# design.net
KiCad netlist of a schematic drawn in Altium Designer
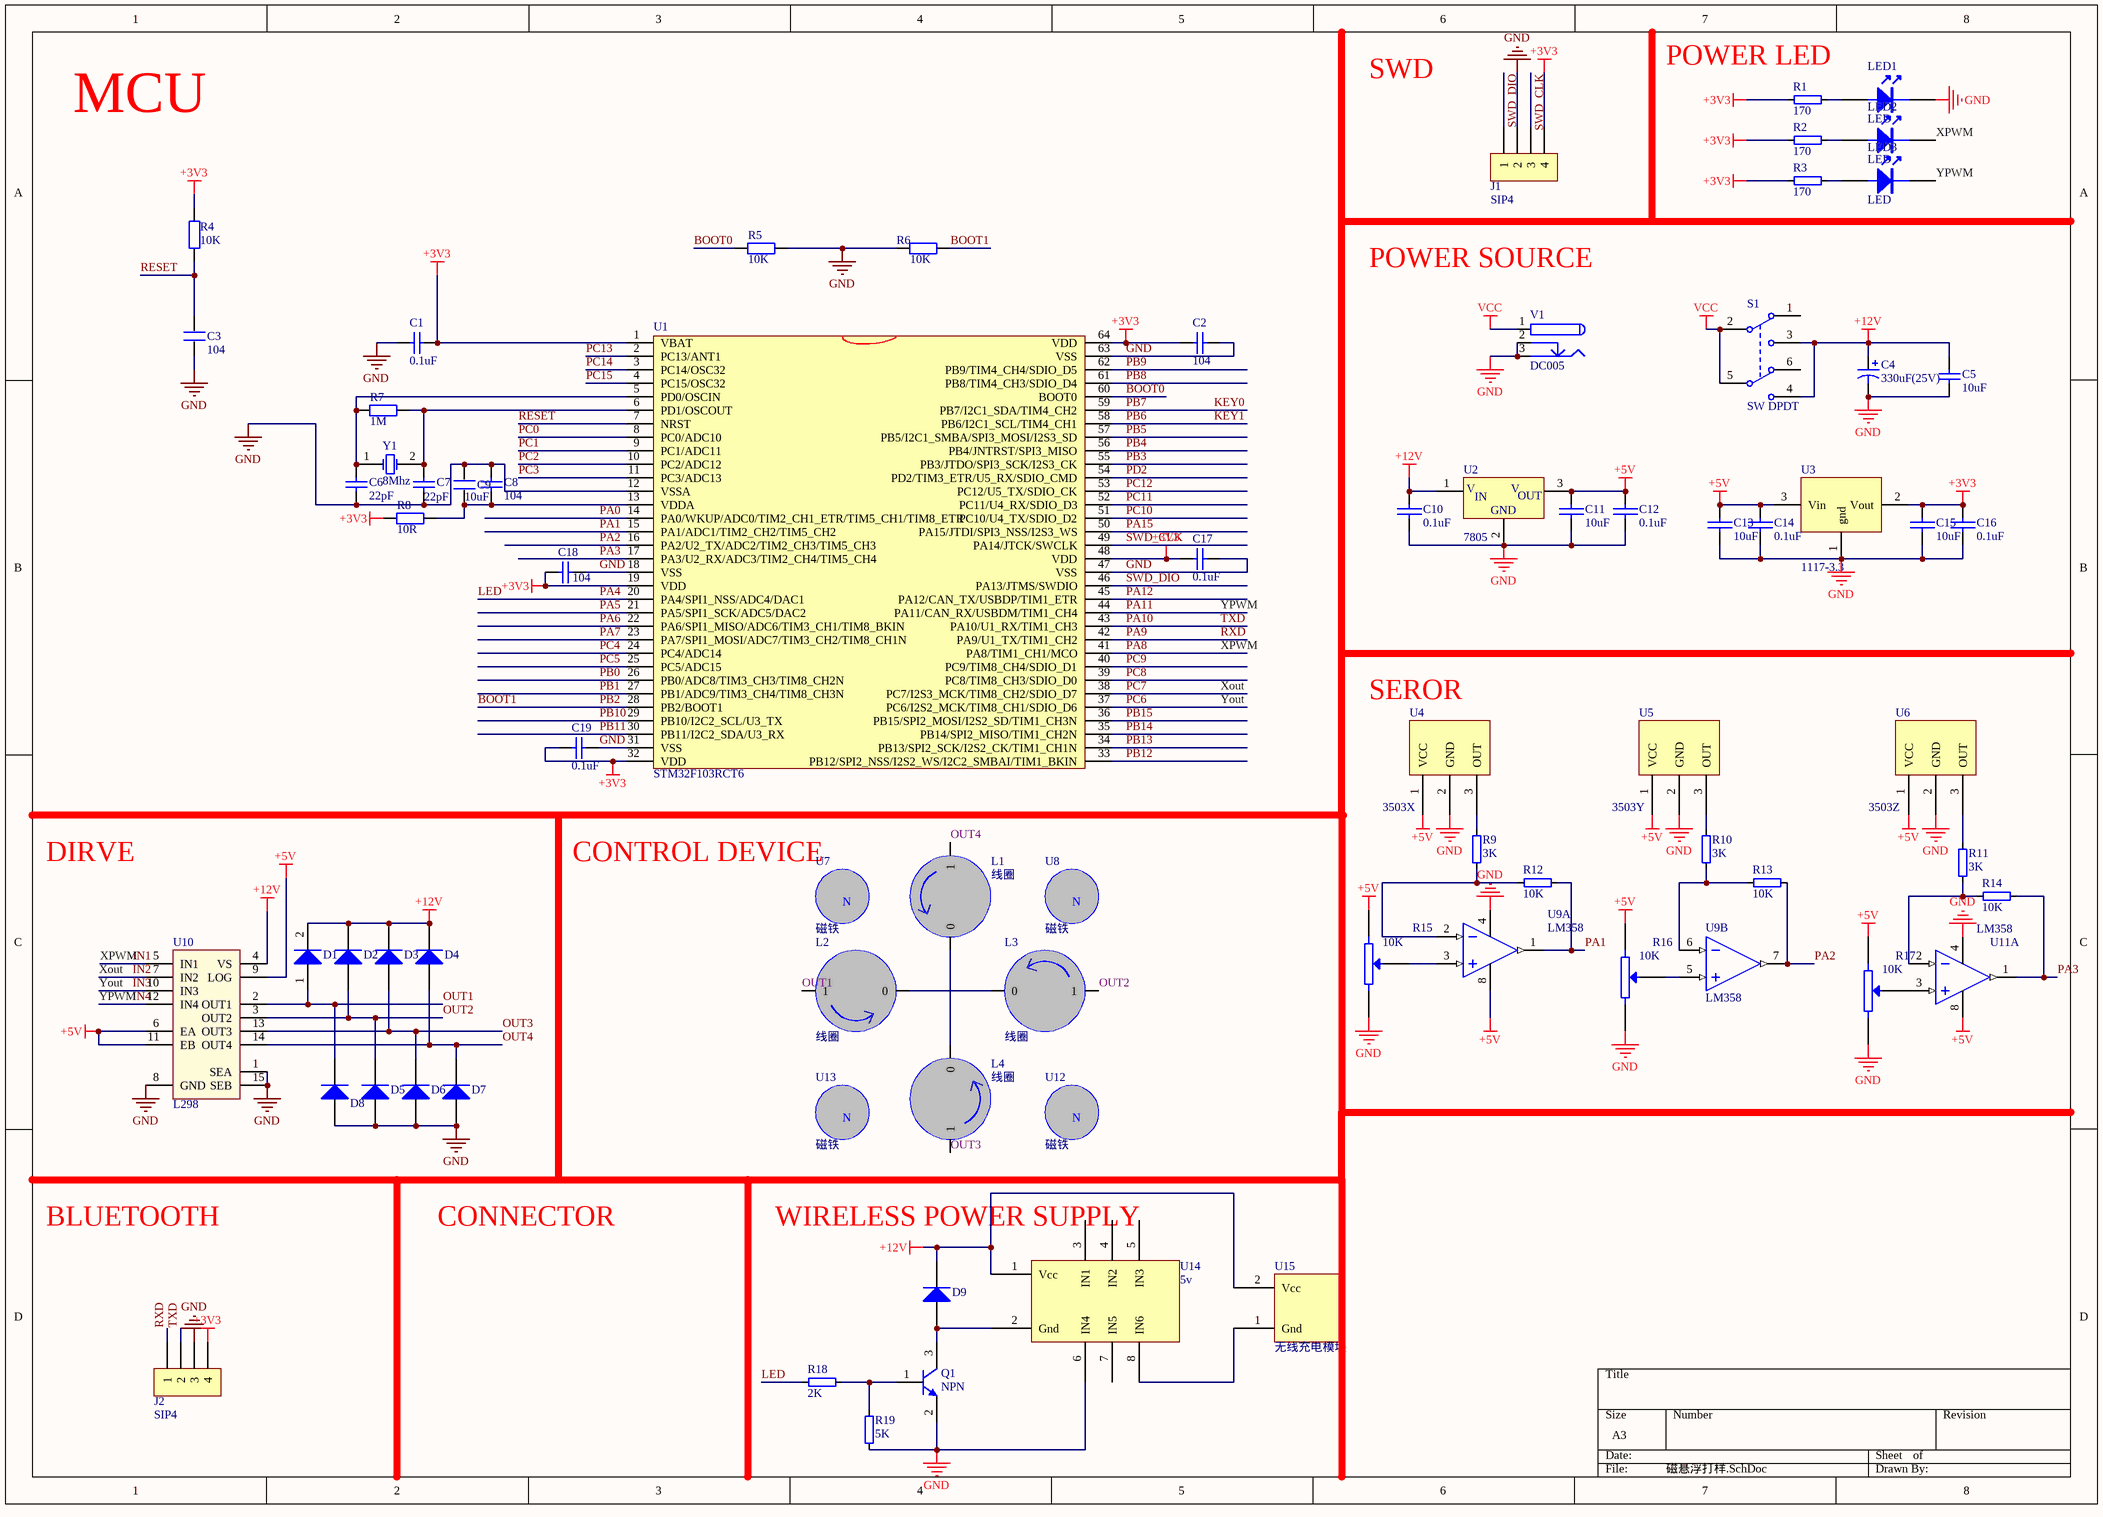
[diagram p0: 磁悬浮打样.SchDoc]

(export (version "E")
  (design (tool "Eeschema 10.0.6"))
  (components
    (comp (ref "C1")
      (value "0.1uF")
      (footprint "CAP_0805")
      (description "Capacitor")
      (fields (field (name "Comment") "Cap") (field (name "PUBLISHER") "Altium Limited"))
      (libsource (lib "FLY") (part "Cap"))
    )
    (comp (ref "C2")
      (value "104")
      (footprint "CAP_0805")
      (description "Capacitor")
      (fields (field (name "Comment") "Cap") (field (name "PUBLISHER") "Altium Limited"))
      (libsource (lib "FLY") (part "Cap_1"))
    )
    (comp (ref "C3") (value "104") (footprint "CAP_0805") (libsource (lib "液晶模块封装库") (part "C")))
    (comp (ref "C4")
      (value "330uF(25V)")
      (footprint "CAP_ELEC_AL_6.3x4.2")
      (description "Polarized Capacitor (Radial)")
      (fields (field (name "Comment") "Cap Pol1") (field (name "PUBLISHER") "Altium Limited"))
      (libsource (lib "FLY") (part "Cap Pol1_1"))
    )
    (comp (ref "C5")
      (value "10uF")
      (footprint "CAP_0805")
      (description "Capacitor")
      (fields (field (name "Comment") "Cap") (field (name "PUBLISHER") "Altium Limited"))
      (libsource (lib "FLY") (part "Cap_2"))
    )
    (comp (ref "C6")
      (value "22pF")
      (footprint "CAP_0805")
      (description "Capacitor")
      (fields (field (name "Comment") "Cap") (field (name "PUBLISHER") "Altium Limited"))
      (libsource (lib "FLY") (part "Cap_3"))
    )
    (comp (ref "C7")
      (value "22pF")
      (footprint "CAP_0805")
      (description "Capacitor")
      (fields (field (name "Comment") "Cap") (field (name "PUBLISHER") "Altium Limited"))
      (libsource (lib "FLY") (part "Cap_3"))
    )
    (comp (ref "C8")
      (value "104")
      (footprint "CAP_0805")
      (description "Capacitor")
      (fields (field (name "Comment") "Cap") (field (name "PUBLISHER") "Altium Limited"))
      (libsource (lib "FLY") (part "Cap_3"))
    )
    (comp (ref "C9") (value "10uF") (footprint "CAP_0805") (libsource (lib "ENC28J60网络模块封装库") (part "C")))
    (comp (ref "C10")
      (value "0.1uF")
      (footprint "CAP_0805")
      (libsource (lib "altium-import") (part "root_0_CAP_"))
    )
    (comp (ref "C11") (value "10uF") (footprint "CAP_0805") (libsource (lib "*") (part "CAP")))
    (comp (ref "C12") (value "0.1uF") (footprint "CAP_0805") (libsource (lib "*") (part "CAP")))
    (comp (ref "C13") (value "10uF") (footprint "CAP_0805") (libsource (lib "*") (part "CAP")))
    (comp (ref "C14") (value "0.1uF") (footprint "CAP_0805") (libsource (lib "*") (part "CAP")))
    (comp (ref "C15") (value "10uF") (footprint "CAP_0805") (libsource (lib "*") (part "CAP")))
    (comp (ref "C16") (value "0.1uF") (footprint "CAP_0805") (libsource (lib "*") (part "CAP")))
    (comp (ref "C17")
      (value "0.1uF")
      (footprint "CAP_0805")
      (description "Capacitor")
      (fields (field (name "Comment") "Cap") (field (name "PUBLISHER") "Altium Limited"))
      (libsource (lib "FLY") (part "Cap_1"))
    )
    (comp (ref "C18")
      (value "104")
      (footprint "CAP_0805")
      (description "Capacitor")
      (fields (field (name "Comment") "Cap") (field (name "PUBLISHER") "Altium Limited"))
      (libsource (lib "FLY") (part "Cap_1"))
    )
    (comp (ref "C19")
      (value "0.1uF")
      (footprint "CAP_0805")
      (description "Capacitor")
      (fields (field (name "Comment") "Cap") (field (name "PUBLISHER") "Altium Limited"))
      (libsource (lib "FLY") (part "Cap_1"))
    )
    (comp (ref "D1")
      (value "Diode")
      (footprint "PCB11:1N5819")
      (description "Default Diode")
      (fields (field (name "PUBLISHER") "Altium Limited"))
      (libsource (lib "") (part "Diode_1"))
    )
    (comp (ref "D2")
      (value "Diode")
      (footprint "PCB11:1N5819")
      (description "Default Diode")
      (fields (field (name "PUBLISHER") "Altium Limited"))
      (libsource (lib "*") (part "Diode"))
    )
    (comp (ref "D3")
      (value "Diode")
      (footprint "PCB11:1N5819")
      (description "Default Diode")
      (fields (field (name "PUBLISHER") "Altium Limited"))
      (libsource (lib "*") (part "Diode"))
    )
    (comp (ref "D4")
      (value "Diode")
      (footprint "PCB11:1N5819")
      (description "Default Diode")
      (fields (field (name "PUBLISHER") "Altium Limited"))
      (libsource (lib "*") (part "Diode"))
    )
    (comp (ref "D5")
      (value "Diode")
      (footprint "PCB11:1N5819")
      (description "Default Diode")
      (fields (field (name "PUBLISHER") "Altium Limited"))
      (libsource (lib "*") (part "Diode"))
    )
    (comp (ref "D6")
      (value "Diode")
      (footprint "PCB11:1N5819")
      (description "Default Diode")
      (fields (field (name "PUBLISHER") "Altium Limited"))
      (libsource (lib "*") (part "Diode"))
    )
    (comp (ref "D7")
      (value "Diode")
      (footprint "PCB11:1N5819")
      (description "Default Diode")
      (fields (field (name "PUBLISHER") "Altium Limited"))
      (libsource (lib "*") (part "Diode"))
    )
    (comp (ref "D8")
      (value "Diode")
      (footprint "PCB11:1N5819")
      (description "Default Diode")
      (fields (field (name "PUBLISHER") "Altium Limited"))
      (libsource (lib "*") (part "Diode"))
    )
    (comp (ref "D9")
      (value "Diode")
      (footprint "PCB11:1N5819")
      (description "Default Diode")
      (fields (field (name "PUBLISHER") "Altium Limited"))
      (libsource (lib "*") (part "Diode"))
    )
    (comp (ref "J1")
      (value "SIP4")
      (footprint "HDR1X4_180_2.54")
      (description "jointbar")
      (libsource (lib "接口") (part "SIP4"))
    )
    (comp (ref "J2")
      (value "SIP4")
      (footprint "298N:SIP4 H")
      (description "jointbar")
      (libsource (lib "接口") (part "SIP4"))
    )
    (comp (ref "L1") (value "线圈") (footprint "线圈") (libsource (lib "红外报警") (part "线圈")))
    (comp (ref "L2") (value "线圈") (footprint "线圈") (libsource (lib "红外报警") (part "线圈")))
    (comp (ref "L3") (value "线圈") (footprint "线圈") (libsource (lib "红外报警") (part "线圈")))
    (comp (ref "L4") (value "线圈") (footprint "线圈") (libsource (lib "红外报警") (part "线圈")))
    (comp (ref "LED1")
      (value "LED")
      (footprint "LED0805蓝")
      (libsource (lib "阻容LED（集成）_Library") (part "LED"))
    )
    (comp (ref "LED2")
      (value "LED")
      (footprint "LED0805蓝")
      (libsource (lib "阻容LED（集成）_Library") (part "LED"))
    )
    (comp (ref "LED3")
      (value "LED")
      (footprint "LED0805蓝")
      (libsource (lib "阻容LED（集成）_Library") (part "LED"))
    )
    (comp (ref "Q1")
      (value "NPN")
      (footprint "SOT23-3")
      (description "贴片三极管")
      (fields (field (name "PUBLISHER") "Altium Limited"))
      (libsource (lib "主库（集成）_Library") (part "NPN1"))
    )
    (comp (ref "R1") (value "170") (footprint "PCB_Passive:RES_0805") (libsource (lib "*") (part "RESistor")))
    (comp (ref "R2") (value "170") (footprint "PCB_Passive:RES_0805") (libsource (lib "*") (part "RESistor")))
    (comp (ref "R3") (value "170") (footprint "PCB_Passive:RES_0805") (libsource (lib "*") (part "RESistor")))
    (comp (ref "R4")
      (value "10K")
      (footprint "RES_0805")
      (description "Resistor")
      (fields (field (name "Comment") "Res2") (field (name "PUBLISHER") "Altium Limited"))
      (libsource (lib "") (part "Res2_1_1"))
    )
    (comp (ref "R5")
      (value "10K")
      (footprint "RES_0805")
      (description "Resistor")
      (fields (field (name "Comment") "Res2") (field (name "PUBLISHER") "Altium Limited"))
      (libsource (lib "FLY") (part "Res2"))
    )
    (comp (ref "R6")
      (value "10K")
      (footprint "RES_0805")
      (description "Resistor")
      (fields (field (name "Comment") "Res2") (field (name "PUBLISHER") "Altium Limited"))
      (libsource (lib "FLY") (part "Res2"))
    )
    (comp (ref "R7")
      (value "1M")
      (footprint "RES_0805")
      (description "Resistor")
      (fields (field (name "Comment") "Res2") (field (name "PUBLISHER") "Altium Limited"))
      (libsource (lib "FLY") (part "Res2"))
    )
    (comp (ref "R8")
      (value "10R")
      (footprint "RES_0805")
      (description "Resistor")
      (fields (field (name "Comment") "Res2") (field (name "PUBLISHER") "Altium Limited"))
      (libsource (lib "FLY") (part "Res2_1"))
    )
    (comp (ref "R9") (value "3K") (footprint "PCB_Passive:RES_0805") (libsource (lib "*") (part "RESistor")))
    (comp (ref "R10") (value "3K") (footprint "PCB_Passive:RES_0805") (libsource (lib "*") (part "RESistor")))
    (comp (ref "R11") (value "3K") (footprint "PCB_Passive:RES_0805") (libsource (lib "*") (part "RESistor")))
    (comp (ref "R12")
      (value "10K")
      (footprint "PCB_Passive:RES_0805")
      (libsource (lib "*") (part "RESistor"))
    )
    (comp (ref "R13")
      (value "10K")
      (footprint "PCB_Passive:RES_0805")
      (libsource (lib "*") (part "RESistor"))
    )
    (comp (ref "R14")
      (value "10K")
      (footprint "PCB_Passive:RES_0805")
      (libsource (lib "*") (part "RESistor"))
    )
    (comp (ref "R15")
      (value "10K")
      (footprint "VR")
      (description "Potentiometer")
      (libsource (lib "原理图") (part "RESVR"))
    )
    (comp (ref "R16")
      (value "10K")
      (footprint "VR")
      (description "Potentiometer")
      (libsource (lib "原理图") (part "RESVR"))
    )
    (comp (ref "R17")
      (value "10K")
      (footprint "VR")
      (description "Potentiometer")
      (libsource (lib "原理图") (part "RESVR"))
    )
    (comp (ref "R18") (value "2K") (footprint "PCB_Passive:RES_0805") (libsource (lib "*") (part "RESistor")))
    (comp (ref "R19") (value "5K") (footprint "PCB_Passive:RES_0805") (libsource (lib "*") (part "RESistor")))
    (comp (ref "S1")
      (value "SW DPDT")
      (footprint "SW6")
      (description "Switch")
      (fields (field (name "PUBLISHER") "Altium Limited"))
      (libsource (lib "原理图") (part "SW DPDT"))
    )
    (comp (ref "U1")
      (value "STM32F103RCT6")
      (footprint "LQFP64_L")
      (libsource (lib "MiniSTM32 V3.0封装库") (part "STM32F103RDT6"))
    )
    (comp (ref "U2") (value "7805") (footprint "TO-220") (libsource (lib "ADDA库") (part "7812")))
    (comp (ref "U3") (value "1117-3.3") (footprint "SOT223") (libsource (lib "298N") (part "1117")))
    (comp (ref "U4") (value "3503X") (footprint "TO-92UA") (libsource (lib "298N") (part "3503")))
    (comp (ref "U5") (value "3503Y") (footprint "TO-92UA") (libsource (lib "298N") (part "3503")))
    (comp (ref "U6") (value "3503Z") (footprint "TO-92UA") (libsource (lib "298N") (part "3503")))
    (comp (ref "U7") (value "磁铁") (footprint "磁铁") (libsource (lib "298N") (part "磁铁")))
    (comp (ref "U8") (value "磁铁") (footprint "磁铁") (libsource (lib "298N") (part "磁铁")))
    (comp (ref "U9")
      (value "LM358")
      (footprint "SOIC-8")
      (description "双运放")
      (libsource (lib "主库（集成）_Library") (part "LM358"))
    )
    (comp (ref "U10") (value "L298") (footprint "L298N") (libsource (lib "leelib") (part "L298")))
    (comp (ref "U11")
      (value "LM358")
      (footprint "SOIC-8")
      (description "双运放")
      (libsource (lib "主库（集成）_Library") (part "LM358"))
    )
    (comp (ref "U12") (value "磁铁") (footprint "磁铁") (libsource (lib "298N") (part "磁铁")))
    (comp (ref "U13") (value "磁铁") (footprint "磁铁") (libsource (lib "298N") (part "磁铁")))
    (comp (ref "U14") (value "5v") (footprint "relay-5v") (libsource (lib "298N") (part "relay-5V")))
    (comp (ref "U15") (value "无线充电模块") (footprint "无线充电模块") (libsource (lib "298N") (part "无线充电")))
    (comp (ref "V1") (value "DC005") (footprint "DC-005") (libsource (lib "原理图") (part "DC005")))
    (comp (ref "Y1")
      (value "8Mhz")
      (footprint "crystal")
      (description "Crystal Oscillator")
      (fields (field (name "PUBLISHER") "Altium Limited"))
      (libsource (lib "*") (part "XTAL"))
    )
  )
  (nets
    (net (code "1") (name "+3V3") (class "Default")
      (node (ref "C1") (pin "2") (pinfunction "2_2") (pintype "passive"))
      (node (ref "C15") (pin "1") (pinfunction "1_1") (pintype "passive"))
      (node (ref "C16") (pin "1") (pinfunction "1_1") (pintype "passive"))
      (node (ref "C17") (pin "1") (pinfunction "1_1") (pintype "passive"))
      (node (ref "C18") (pin "1") (pinfunction "1_1") (pintype "passive"))
      (node (ref "C19") (pin "1") (pinfunction "1_1") (pintype "passive"))
      (node (ref "C2") (pin "1") (pinfunction "1_1") (pintype "passive"))
      (node (ref "J1") (pin "4") (pinfunction "4_4") (pintype "passive"))
      (node (ref "J2") (pin "4") (pinfunction "4_4") (pintype "passive"))
      (node (ref "R1") (pin "1") (pinfunction "1_1") (pintype "passive"))
      (node (ref "R2") (pin "1") (pinfunction "1_1") (pintype "passive"))
      (node (ref "R3") (pin "1") (pinfunction "1_1") (pintype "passive"))
      (node (ref "R4") (pin "2") (pinfunction "2_2") (pintype "passive"))
      (node (ref "R8") (pin "1") (pinfunction "1_1") (pintype "passive"))
      (node (ref "U1") (pin "1") (pinfunction "VBAT_1") (pintype "passive"))
      (node (ref "U1") (pin "19") (pinfunction "VDD_19") (pintype "passive"))
      (node (ref "U1") (pin "32") (pinfunction "VDD_32") (pintype "passive"))
      (node (ref "U1") (pin "48") (pinfunction "VDD_48") (pintype "passive"))
      (node (ref "U1") (pin "64") (pinfunction "VDD_64") (pintype "passive"))
      (node (ref "U3") (pin "2") (pinfunction "Vout_2") (pintype "passive"))
    )
    (net (code "2") (name "+5V") (class "Default")
      (node (ref "C11") (pin "1") (pinfunction "1_1") (pintype "passive"))
      (node (ref "C12") (pin "1") (pinfunction "1_1") (pintype "passive"))
      (node (ref "C13") (pin "1") (pinfunction "1_1") (pintype "passive"))
      (node (ref "C14") (pin "1") (pinfunction "1_1") (pintype "passive"))
      (node (ref "R15") (pin "1") (pinfunction "1_1") (pintype "passive"))
      (node (ref "R16") (pin "1") (pinfunction "1_1") (pintype "passive"))
      (node (ref "R17") (pin "1") (pinfunction "1_1") (pintype "passive"))
      (node (ref "U10") (pin "11") (pinfunction "EB_11") (pintype "passive"))
      (node (ref "U10") (pin "6") (pinfunction "EA_6") (pintype "passive"))
      (node (ref "U10") (pin "9") (pinfunction "LOG_9") (pintype "passive"))
      (node (ref "U11") (pin "8") (pinfunction "V+_8") (pintype "passive"))
      (node (ref "U2") (pin "3") (pinfunction "VOUT_3") (pintype "passive"))
      (node (ref "U3") (pin "3") (pinfunction "Vin_3") (pintype "passive"))
      (node (ref "U4") (pin "1") (pinfunction "VCC_1") (pintype "passive"))
      (node (ref "U5") (pin "1") (pinfunction "VCC_1") (pintype "passive"))
      (node (ref "U6") (pin "1") (pinfunction "VCC_1") (pintype "passive"))
      (node (ref "U9") (pin "8") (pinfunction "V+_8") (pintype "passive"))
    )
    (net (code "3") (name "+12V") (class "Default")
      (node (ref "C10") (pin "1") (pinfunction "1_1") (pintype "passive"))
      (node (ref "C4") (pin "1") (pinfunction "1_1") (pintype "passive"))
      (node (ref "C5") (pin "2") (pinfunction "2_2") (pintype "passive"))
      (node (ref "D1") (pin "2") (pinfunction "K_2") (pintype "passive"))
      (node (ref "D2") (pin "2") (pinfunction "K_2") (pintype "passive"))
      (node (ref "D3") (pin "2") (pinfunction "K_2") (pintype "passive"))
      (node (ref "D4") (pin "2") (pinfunction "K_2") (pintype "passive"))
      (node (ref "D9") (pin "2") (pinfunction "K_2") (pintype "passive"))
      (node (ref "S1") (pin "3") (pinfunction "NO1_3") (pintype "passive"))
      (node (ref "S1") (pin "4") (pinfunction "NO2_4") (pintype "passive"))
      (node (ref "U10") (pin "4") (pinfunction "VS_4") (pintype "passive"))
      (node (ref "U14") (pin "1") (pinfunction "Vcc_1") (pintype "passive"))
      (node (ref "U15") (pin "2") (pinfunction "Vcc_2") (pintype "passive"))
      (node (ref "U2") (pin "1") (pinfunction "VIN_1") (pintype "passive"))
    )
    (net (code "4") (name "/BOOT0") (class "Default")
      (node (ref "R5") (pin "1") (pinfunction "1_1") (pintype "passive"))
      (node (ref "U1") (pin "60") (pinfunction "BOOT0_60") (pintype "passive"))
    )
    (net (code "5") (name "/BOOT1") (class "Default")
      (node (ref "R6") (pin "2") (pinfunction "2_2") (pintype "passive"))
      (node (ref "U1") (pin "28") (pinfunction "PB2/BOOT1_28") (pintype "passive"))
    )
    (net (code "6") (name "/IN1") (class "Default")
      (node (ref "LED2") (pin "K") (pinfunction "2_K") (pintype "passive"))
      (node (ref "U1") (pin "41") (pinfunction "PA8/TIM1_CH1/MCO_41") (pintype "passive"))
      (node (ref "U10") (pin "5") (pinfunction "IN1_5") (pintype "passive"))
    )
    (net (code "7") (name "/IN2") (class "Default")
      (node (ref "U1") (pin "38") (pinfunction "PC7/I2S3_MCK/TIM8_CH2/SDIO_D7_38") (pintype "passive"))
      (node (ref "U10") (pin "7") (pinfunction "IN2_7") (pintype "passive"))
    )
    (net (code "8") (name "/IN3") (class "Default")
      (node (ref "U1") (pin "37") (pinfunction "PC6/I2S2_MCK/TIM8_CH1/SDIO_D6_37") (pintype "passive"))
      (node (ref "U10") (pin "10") (pinfunction "IN3_10") (pintype "passive"))
    )
    (net (code "9") (name "/IN4") (class "Default")
      (node (ref "LED3") (pin "K") (pinfunction "2_K") (pintype "passive"))
      (node (ref "U1") (pin "44") (pinfunction "PA11/CAN_RX/USBDM/TIM1_CH4_44") (pintype "passive"))
      (node (ref "U10") (pin "12") (pinfunction "IN4_12") (pintype "passive"))
    )
    (net (code "10") (name "/KEY0") (class "Default")
      (node (ref "U1") (pin "59") (pinfunction "PB7/I2C1_SDA/TIM4_CH2_59") (pintype "passive"))
    )
    (net (code "11") (name "/KEY1") (class "Default")
      (node (ref "U1") (pin "58") (pinfunction "PB6/I2C1_SCL/TIM4_CH1_58") (pintype "passive"))
    )
    (net (code "12") (name "/LED") (class "Default")
      (node (ref "R18") (pin "2") (pinfunction "2_2") (pintype "passive"))
      (node (ref "U1") (pin "20") (pinfunction "PA4/SPI1_NSS/ADC4/DAC1_20") (pintype "passive"))
    )
    (net (code "13") (name "/OUT1") (class "Default")
      (node (ref "D1") (pin "1") (pinfunction "A_1") (pintype "passive"))
      (node (ref "D8") (pin "2") (pinfunction "K_2") (pintype "passive"))
      (node (ref "L2") (pin "1") (pinfunction "1_1") (pintype "passive"))
      (node (ref "U10") (pin "2") (pinfunction "OUT1_2") (pintype "passive"))
    )
    (net (code "14") (name "/OUT2") (class "Default")
      (node (ref "D2") (pin "1") (pinfunction "A_1") (pintype "passive"))
      (node (ref "D5") (pin "2") (pinfunction "K_2") (pintype "passive"))
      (node (ref "L3") (pin "1") (pinfunction "1_1") (pintype "passive"))
      (node (ref "U10") (pin "3") (pinfunction "OUT2_3") (pintype "passive"))
    )
    (net (code "15") (name "/OUT3") (class "Default")
      (node (ref "D3") (pin "1") (pinfunction "A_1") (pintype "passive"))
      (node (ref "D6") (pin "2") (pinfunction "K_2") (pintype "passive"))
      (node (ref "L4") (pin "1") (pinfunction "1_1") (pintype "passive"))
      (node (ref "U10") (pin "13") (pinfunction "OUT3_13") (pintype "passive"))
    )
    (net (code "16") (name "/OUT4") (class "Default")
      (node (ref "D4") (pin "1") (pinfunction "A_1") (pintype "passive"))
      (node (ref "D7") (pin "2") (pinfunction "K_2") (pintype "passive"))
      (node (ref "L1") (pin "1") (pinfunction "1_1") (pintype "passive"))
      (node (ref "U10") (pin "14") (pinfunction "OUT4_14") (pintype "passive"))
    )
    (net (code "17") (name "/PA0") (class "Default")
      (node (ref "U1") (pin "14") (pinfunction "PA0/WKUP/ADC0/TIM2_CH1_ETR/TIM5_CH1/TIM8_ETR_14") (pintype "passive"))
    )
    (net (code "18") (name "/PA1") (class "Default")
      (node (ref "R12") (pin "1") (pinfunction "1_1") (pintype "passive"))
      (node (ref "U1") (pin "15") (pinfunction "PA1/ADC1/TIM2_CH2/TIM5_CH2_15") (pintype "passive"))
      (node (ref "U9") (pin "1") (pinfunction "OUT_1") (pintype "output"))
    )
    (net (code "19") (name "/PA2") (class "Default")
      (node (ref "R13") (pin "1") (pinfunction "1_1") (pintype "passive"))
      (node (ref "U1") (pin "16") (pinfunction "PA2/U2_TX/ADC2/TIM2_CH3/TIM5_CH3_16") (pintype "passive"))
      (node (ref "U9") (pin "7") (pinfunction "OUT_7") (pintype "output"))
    )
    (net (code "20") (name "/PA3") (class "Default")
      (node (ref "R14") (pin "1") (pinfunction "1_1") (pintype "passive"))
      (node (ref "U1") (pin "17") (pinfunction "PA3/U2_RX/ADC3/TIM2_CH4/TIM5_CH4_17") (pintype "passive"))
      (node (ref "U11") (pin "1") (pinfunction "OUT_1") (pintype "output"))
    )
    (net (code "21") (name "/PA5") (class "Default")
      (node (ref "U1") (pin "21") (pinfunction "PA5/SPI1_SCK/ADC5/DAC2_21") (pintype "passive"))
    )
    (net (code "22") (name "/PA6") (class "Default")
      (node (ref "U1") (pin "22") (pinfunction "PA6/SPI1_MISO/ADC6/TIM3_CH1/TIM8_BKIN_22") (pintype "passive"))
    )
    (net (code "23") (name "/PA7") (class "Default")
      (node (ref "U1") (pin "23") (pinfunction "PA7/SPI1_MOSI/ADC7/TIM3_CH2/TIM8_CH1N_23") (pintype "passive"))
    )
    (net (code "24") (name "/PA9") (class "Default")
      (node (ref "J2") (pin "1") (pinfunction "1_1") (pintype "passive"))
      (node (ref "U1") (pin "42") (pinfunction "PA9/U1_TX/TIM1_CH2_42") (pintype "passive"))
    )
    (net (code "25") (name "/PA10") (class "Default")
      (node (ref "J2") (pin "2") (pinfunction "2_2") (pintype "passive"))
      (node (ref "U1") (pin "43") (pinfunction "PA10/U1_RX/TIM1_CH3_43") (pintype "passive"))
    )
    (net (code "26") (name "/PA12") (class "Default")
      (node (ref "U1") (pin "45") (pinfunction "PA12/CAN_TX/USBDP/TIM1_ETR_45") (pintype "passive"))
    )
    (net (code "27") (name "/PA15") (class "Default")
      (node (ref "U1") (pin "50") (pinfunction "PA15/JTDI/SPI3_NSS/I2S3_WS_50") (pintype "passive"))
    )
    (net (code "28") (name "/PB0") (class "Default")
      (node (ref "U1") (pin "26") (pinfunction "PB0/ADC8/TIM3_CH3/TIM8_CH2N_26") (pintype "passive"))
    )
    (net (code "29") (name "/PB1") (class "Default")
      (node (ref "U1") (pin "27") (pinfunction "PB1/ADC9/TIM3_CH4/TIM8_CH3N_27") (pintype "passive"))
    )
    (net (code "30") (name "/PB3") (class "Default")
      (node (ref "U1") (pin "55") (pinfunction "PB3/JTDO/SPI3_SCK/I2S3_CK_55") (pintype "passive"))
    )
    (net (code "31") (name "/PB4") (class "Default")
      (node (ref "U1") (pin "56") (pinfunction "PB4/JNTRST/SPI3_MISO_56") (pintype "passive"))
    )
    (net (code "32") (name "/PB5") (class "Default")
      (node (ref "U1") (pin "57") (pinfunction "PB5/I2C1_SMBA/SPI3_MOSI/I2S3_SD_57") (pintype "passive"))
    )
    (net (code "33") (name "/PB8") (class "Default")
      (node (ref "U1") (pin "61") (pinfunction "PB8/TIM4_CH3/SDIO_D4_61") (pintype "passive"))
    )
    (net (code "34") (name "/PB9") (class "Default")
      (node (ref "U1") (pin "62") (pinfunction "PB9/TIM4_CH4/SDIO_D5_62") (pintype "passive"))
    )
    (net (code "35") (name "/PB10") (class "Default")
      (node (ref "U1") (pin "29") (pinfunction "PB10/I2C2_SCL/U3_TX_29") (pintype "passive"))
    )
    (net (code "36") (name "/PB11") (class "Default")
      (node (ref "U1") (pin "30") (pinfunction "PB11/I2C2_SDA/U3_RX_30") (pintype "passive"))
    )
    (net (code "37") (name "/PB12") (class "Default")
      (node (ref "U1") (pin "33") (pinfunction "PB12/SPI2_NSS/I2S2_WS/I2C2_SMBAI/TIM1_BKIN_33") (pintype "passive"))
    )
    (net (code "38") (name "/PB13") (class "Default")
      (node (ref "U1") (pin "34") (pinfunction "PB13/SPI2_SCK/I2S2_CK/TIM1_CH1N_34") (pintype "passive"))
    )
    (net (code "39") (name "/PB14") (class "Default")
      (node (ref "U1") (pin "35") (pinfunction "PB14/SPI2_MISO/TIM1_CH2N_35") (pintype "passive"))
    )
    (net (code "40") (name "/PB15") (class "Default")
      (node (ref "U1") (pin "36") (pinfunction "PB15/SPI2_MOSI/I2S2_SD/TIM1_CH3N_36") (pintype "passive"))
    )
    (net (code "41") (name "/PC0") (class "Default")
      (node (ref "U1") (pin "8") (pinfunction "PC0/ADC10_8") (pintype "passive"))
    )
    (net (code "42") (name "/PC1") (class "Default")
      (node (ref "U1") (pin "9") (pinfunction "PC1/ADC11_9") (pintype "passive"))
    )
    (net (code "43") (name "/PC2") (class "Default")
      (node (ref "U1") (pin "10") (pinfunction "PC2/ADC12_10") (pintype "passive"))
    )
    (net (code "44") (name "/PC3") (class "Default")
      (node (ref "U1") (pin "11") (pinfunction "PC3/ADC13_11") (pintype "passive"))
    )
    (net (code "45") (name "/PC4") (class "Default")
      (node (ref "U1") (pin "24") (pinfunction "PC4/ADC14_24") (pintype "passive"))
    )
    (net (code "46") (name "/PC5") (class "Default")
      (node (ref "U1") (pin "25") (pinfunction "PC5/ADC15_25") (pintype "passive"))
    )
    (net (code "47") (name "/PC8") (class "Default")
      (node (ref "U1") (pin "39") (pinfunction "PC8/TIM8_CH3/SDIO_D0_39") (pintype "passive"))
    )
    (net (code "48") (name "/PC9") (class "Default")
      (node (ref "U1") (pin "40") (pinfunction "PC9/TIM8_CH4/SDIO_D1_40") (pintype "passive"))
    )
    (net (code "49") (name "/PC10") (class "Default")
      (node (ref "U1") (pin "51") (pinfunction "PC10/U4_TX/SDIO_D2_51") (pintype "passive"))
    )
    (net (code "50") (name "/PC11") (class "Default")
      (node (ref "U1") (pin "52") (pinfunction "PC11/U4_RX/SDIO_D3_52") (pintype "passive"))
    )
    (net (code "51") (name "/PC12") (class "Default")
      (node (ref "U1") (pin "53") (pinfunction "PC12/U5_TX/SDIO_CK_53") (pintype "passive"))
    )
    (net (code "52") (name "/PC13") (class "Default")
      (node (ref "U1") (pin "2") (pinfunction "PC13/ANT1_2") (pintype "passive"))
    )
    (net (code "53") (name "/PC14") (class "Default")
      (node (ref "U1") (pin "3") (pinfunction "PC14/OSC32_3") (pintype "passive"))
    )
    (net (code "54") (name "/PC15") (class "Default")
      (node (ref "U1") (pin "4") (pinfunction "PC15/OSC32_4") (pintype "passive"))
    )
    (net (code "55") (name "/PD2") (class "Default")
      (node (ref "U1") (pin "54") (pinfunction "PD2/TIM3_ETR/U5_RX/SDIO_CMD_54") (pintype "passive"))
    )
    (net (code "56") (name "/RESET") (class "Default")
      (node (ref "C3") (pin "2") (pintype "passive"))
      (node (ref "R4") (pin "1") (pinfunction "1_1") (pintype "passive"))
      (node (ref "U1") (pin "7") (pinfunction "NRST_7") (pintype "passive"))
    )
    (net (code "57") (name "/SWD_CLK") (class "Default")
      (node (ref "J1") (pin "3") (pinfunction "3_3") (pintype "passive"))
      (node (ref "U1") (pin "49") (pinfunction "PA14/JTCK/SWCLK_49") (pintype "passive"))
    )
    (net (code "58") (name "/SWD_DIO") (class "Default")
      (node (ref "J1") (pin "1") (pinfunction "1_1") (pintype "passive"))
      (node (ref "U1") (pin "46") (pinfunction "PA13/JTMS/SWDIO_46") (pintype "passive"))
    )
    (net (code "59") (name "GND") (class "Default")
      (node (ref "C1") (pin "1") (pinfunction "1_1") (pintype "passive"))
      (node (ref "C10") (pin "2") (pinfunction "2_2") (pintype "passive"))
      (node (ref "C11") (pin "2") (pinfunction "2_2") (pintype "passive"))
      (node (ref "C12") (pin "2") (pinfunction "2_2") (pintype "passive"))
      (node (ref "C13") (pin "2") (pinfunction "2_2") (pintype "passive"))
      (node (ref "C14") (pin "2") (pinfunction "2_2") (pintype "passive"))
      (node (ref "C15") (pin "2") (pinfunction "2_2") (pintype "passive"))
      (node (ref "C16") (pin "2") (pinfunction "2_2") (pintype "passive"))
      (node (ref "C17") (pin "2") (pinfunction "2_2") (pintype "passive"))
      (node (ref "C18") (pin "2") (pinfunction "2_2") (pintype "passive"))
      (node (ref "C19") (pin "2") (pinfunction "2_2") (pintype "passive"))
      (node (ref "C2") (pin "2") (pinfunction "2_2") (pintype "passive"))
      (node (ref "C3") (pin "1") (pintype "passive"))
      (node (ref "C4") (pin "2") (pinfunction "2_2") (pintype "passive"))
      (node (ref "C5") (pin "1") (pinfunction "1_1") (pintype "passive"))
      (node (ref "C6") (pin "1") (pinfunction "1_1") (pintype "passive"))
      (node (ref "C7") (pin "1") (pinfunction "1_1") (pintype "passive"))
      (node (ref "C8") (pin "2") (pinfunction "2_2") (pintype "passive"))
      (node (ref "C9") (pin "2") (pintype "passive"))
      (node (ref "D5") (pin "1") (pinfunction "A_1") (pintype "passive"))
      (node (ref "D6") (pin "1") (pinfunction "A_1") (pintype "passive"))
      (node (ref "D7") (pin "1") (pinfunction "A_1") (pintype "passive"))
      (node (ref "D8") (pin "1") (pinfunction "A_1") (pintype "passive"))
      (node (ref "J1") (pin "2") (pinfunction "2_2") (pintype "passive"))
      (node (ref "J2") (pin "3") (pinfunction "3_3") (pintype "passive"))
      (node (ref "LED1") (pin "K") (pinfunction "2_K") (pintype "passive"))
      (node (ref "Q1") (pin "2") (pinfunction "E_2") (pintype "passive"))
      (node (ref "R15") (pin "2") (pinfunction "2_2") (pintype "passive"))
      (node (ref "R16") (pin "2") (pinfunction "2_2") (pintype "passive"))
      (node (ref "R17") (pin "2") (pinfunction "2_2") (pintype "passive"))
      (node (ref "R19") (pin "2") (pinfunction "2_2") (pintype "passive"))
      (node (ref "R5") (pin "2") (pinfunction "2_2") (pintype "passive"))
      (node (ref "R6") (pin "1") (pinfunction "1_1") (pintype "passive"))
      (node (ref "U1") (pin "12") (pinfunction "VSSA_12") (pintype "passive"))
      (node (ref "U1") (pin "18") (pinfunction "VSS_18") (pintype "passive"))
      (node (ref "U1") (pin "31") (pinfunction "VSS_31") (pintype "passive"))
      (node (ref "U1") (pin "47") (pinfunction "VSS_47") (pintype "passive"))
      (node (ref "U1") (pin "63") (pinfunction "VSS_63") (pintype "passive"))
      (node (ref "U10") (pin "1") (pinfunction "SEA_1") (pintype "passive"))
      (node (ref "U10") (pin "15") (pinfunction "SEB_15") (pintype "passive"))
      (node (ref "U10") (pin "8") (pinfunction "GND_8") (pintype "passive"))
      (node (ref "U11") (pin "4") (pinfunction "V-_4") (pintype "passive"))
      (node (ref "U14") (pin "6") (pinfunction "IN4_6") (pintype "passive"))
      (node (ref "U2") (pin "2") (pinfunction "GND_2") (pintype "passive"))
      (node (ref "U3") (pin "1") (pinfunction "gnd_1") (pintype "passive"))
      (node (ref "U4") (pin "2") (pinfunction "GND_2") (pintype "passive"))
      (node (ref "U5") (pin "2") (pinfunction "GND_2") (pintype "passive"))
      (node (ref "U6") (pin "2") (pinfunction "GND_2") (pintype "passive"))
      (node (ref "U9") (pin "4") (pinfunction "V-_4") (pintype "passive"))
      (node (ref "V1") (pin "2") (pinfunction "3B_2") (pintype "power_in"))
      (node (ref "V1") (pin "3") (pinfunction "3_3") (pintype "power_in"))
    )
    (net (code "60") (name "Net-(D9-A)") (class "Default")
      (node (ref "D9") (pin "1") (pinfunction "A_1") (pintype "passive"))
      (node (ref "Q1") (pin "3") (pinfunction "C_3") (pintype "passive"))
      (node (ref "U14") (pin "2") (pinfunction "Gnd_2") (pintype "passive"))
    )
    (net (code "61") (name "Net-(L1-Pad0)") (class "Default")
      (node (ref "L1") (pin "0") (pinfunction "0_0") (pintype "passive"))
      (node (ref "L4") (pin "0") (pinfunction "0_0") (pintype "passive"))
    )
    (net (code "62") (name "Net-(L2-Pad0)") (class "Default")
      (node (ref "L2") (pin "0") (pinfunction "0_0") (pintype "passive"))
      (node (ref "L3") (pin "0") (pinfunction "0_0") (pintype "passive"))
    )
    (net (code "63") (name "Net-(LED1-1)") (class "Default")
      (node (ref "LED1") (pin "A") (pinfunction "1_A") (pintype "passive"))
      (node (ref "R1") (pin "2") (pinfunction "2_2") (pintype "passive"))
    )
    (net (code "64") (name "Net-(LED2-1)") (class "Default")
      (node (ref "LED2") (pin "A") (pinfunction "1_A") (pintype "passive"))
      (node (ref "R2") (pin "2") (pinfunction "2_2") (pintype "passive"))
    )
    (net (code "65") (name "Net-(LED3-1)") (class "Default")
      (node (ref "LED3") (pin "A") (pinfunction "1_A") (pintype "passive"))
      (node (ref "R3") (pin "2") (pinfunction "2_2") (pintype "passive"))
    )
    (net (code "66") (name "Net-(Q1-B)") (class "Default")
      (node (ref "Q1") (pin "1") (pinfunction "B_1") (pintype "passive"))
      (node (ref "R18") (pin "1") (pinfunction "1_1") (pintype "passive"))
      (node (ref "R19") (pin "1") (pinfunction "1_1") (pintype "passive"))
    )
    (net (code "67") (name "Net-(R15-W)") (class "Default")
      (node (ref "R15") (pin "3") (pinfunction "W_3") (pintype "passive"))
      (node (ref "U9") (pin "3") (pinfunction "IN+_3") (pintype "input"))
    )
    (net (code "68") (name "Net-(R16-W)") (class "Default")
      (node (ref "R16") (pin "3") (pinfunction "W_3") (pintype "passive"))
      (node (ref "U9") (pin "5") (pinfunction "IN+_5") (pintype "input"))
    )
    (net (code "69") (name "Net-(R17-W)") (class "Default")
      (node (ref "R17") (pin "3") (pinfunction "W_3") (pintype "passive"))
      (node (ref "U11") (pin "3") (pinfunction "IN+_3") (pintype "input"))
    )
    (net (code "70") (name "Net-(U1-PD0{slash}OSCIN)") (class "Default")
      (node (ref "C6") (pin "2") (pinfunction "2_2") (pintype "passive"))
      (node (ref "R7") (pin "1") (pinfunction "1_1") (pintype "passive"))
      (node (ref "U1") (pin "5") (pinfunction "PD0/OSCIN_5") (pintype "passive"))
      (node (ref "Y1") (pin "1") (pinfunction "OSC1_1") (pintype "passive"))
    )
    (net (code "71") (name "Net-(U1-PD1{slash}OSCOUT)") (class "Default")
      (node (ref "C7") (pin "2") (pinfunction "2_2") (pintype "passive"))
      (node (ref "R7") (pin "2") (pinfunction "2_2") (pintype "passive"))
      (node (ref "U1") (pin "6") (pinfunction "PD1/OSCOUT_6") (pintype "passive"))
      (node (ref "Y1") (pin "2") (pinfunction "OSC2_2") (pintype "passive"))
    )
    (net (code "72") (name "Net-(U1-VDDA)") (class "Default")
      (node (ref "C8") (pin "1") (pinfunction "1_1") (pintype "passive"))
      (node (ref "C9") (pin "1") (pintype "passive"))
      (node (ref "R8") (pin "2") (pinfunction "2_2") (pintype "passive"))
      (node (ref "U1") (pin "13") (pinfunction "VDDA_13") (pintype "passive"))
    )
    (net (code "73") (name "Net-(U4-OUT)") (class "Default")
      (node (ref "R9") (pin "2") (pinfunction "2_2") (pintype "passive"))
      (node (ref "U4") (pin "3") (pinfunction "OUT_3") (pintype "passive"))
    )
    (net (code "74") (name "Net-(U5-OUT)") (class "Default")
      (node (ref "R10") (pin "2") (pinfunction "2_2") (pintype "passive"))
      (node (ref "U5") (pin "3") (pinfunction "OUT_3") (pintype "passive"))
    )
    (net (code "75") (name "Net-(U6-OUT)") (class "Default")
      (node (ref "R11") (pin "2") (pinfunction "2_2") (pintype "passive"))
      (node (ref "U6") (pin "3") (pinfunction "OUT_3") (pintype "passive"))
    )
    (net (code "76") (name "Net-(U9A-IN-)") (class "Default")
      (node (ref "R12") (pin "2") (pinfunction "2_2") (pintype "passive"))
      (node (ref "R9") (pin "1") (pinfunction "1_1") (pintype "passive"))
      (node (ref "U9") (pin "2") (pinfunction "IN-_2") (pintype "input"))
    )
    (net (code "77") (name "Net-(U9B-IN-)") (class "Default")
      (node (ref "R10") (pin "1") (pinfunction "1_1") (pintype "passive"))
      (node (ref "R13") (pin "2") (pinfunction "2_2") (pintype "passive"))
      (node (ref "U9") (pin "6") (pinfunction "IN-_6") (pintype "input"))
    )
    (net (code "78") (name "Net-(U11A-IN-)") (class "Default")
      (node (ref "R11") (pin "1") (pinfunction "1_1") (pintype "passive"))
      (node (ref "R14") (pin "2") (pinfunction "2_2") (pintype "passive"))
      (node (ref "U11") (pin "2") (pinfunction "IN-_2") (pintype "input"))
    )
    (net (code "79") (name "Net-(U14-IN6)") (class "Default")
      (node (ref "U14") (pin "8") (pinfunction "IN6_8") (pintype "passive"))
      (node (ref "U15") (pin "1") (pinfunction "Gnd_1") (pintype "passive"))
    )
    (net (code "80") (name "VCC") (class "Default")
      (node (ref "S1") (pin "2") (pinfunction "COMMON1_2") (pintype "passive"))
      (node (ref "S1") (pin "5") (pinfunction "COMMON2_5") (pintype "passive"))
      (node (ref "V1") (pin "1") (pinfunction "1_1") (pintype "power_in"))
    )
    (net (code "81") (name "unconnected-(S1-NC1-Pad1)") (class "Default")
      (node (ref "S1") (pin "1") (pinfunction "NC1_1") (pintype "passive"))
    )
    (net (code "82") (name "unconnected-(S1-NC2-Pad6)") (class "Default")
      (node (ref "S1") (pin "6") (pinfunction "NC2_6") (pintype "passive"))
    )
    (net (code "83") (name "unconnected-(U14-IN1-Pad3)") (class "Default")
      (node (ref "U14") (pin "3") (pinfunction "IN1_3") (pintype "passive"))
    )
    (net (code "84") (name "unconnected-(U14-IN2-Pad4)") (class "Default")
      (node (ref "U14") (pin "4") (pinfunction "IN2_4") (pintype "passive"))
    )
    (net (code "85") (name "unconnected-(U14-IN3-Pad5)") (class "Default")
      (node (ref "U14") (pin "5") (pinfunction "IN3_5") (pintype "passive"))
    )
    (net (code "86") (name "unconnected-(U14-IN5-Pad7)") (class "Default")
      (node (ref "U14") (pin "7") (pinfunction "IN5_7") (pintype "passive"))
    )
  )
)
